# prec_3V_LDO.net
KiCad netlist of a schematic drawn in Altium Designer
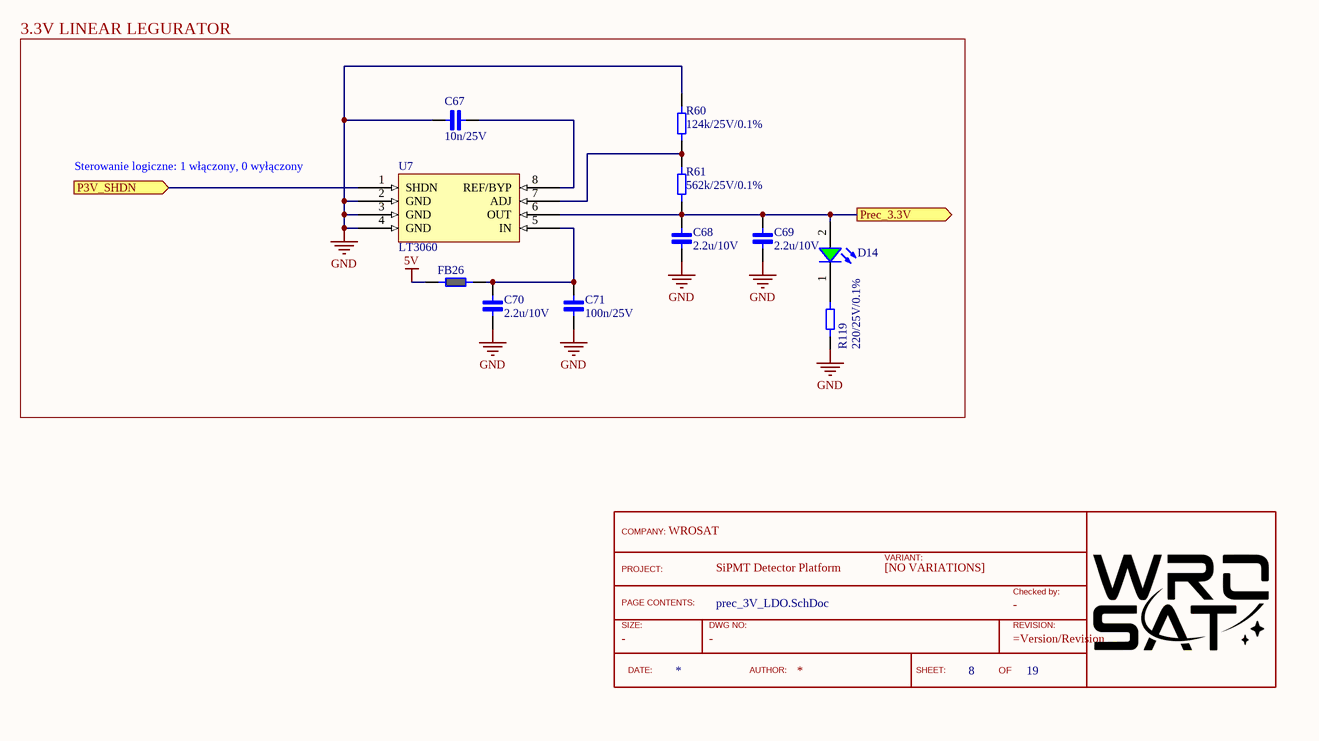
[diagram p0: prec_3V_LDO.SchDoc]

(export (version "E")
  (design (tool "Eeschema 10.0.6"))
  (components
    (comp (ref "C67")
      (value "10n/25V")
      (footprint "Cap_0402")
      (description "Ceramic Capacitor 10n / 0402 / 25V / ±5%, Wurth Elektronik MLCC")
      (libsource (lib "Cubesat_lib") (part "Cap_0402_10n"))
    )
    (comp (ref "C68")
      (value "2.2u/10V")
      (footprint "Cap_0402")
      (description "Ceramic Capacitor 2.2uF / 0402 / 10V / ±5%, Wurth Elektronik MLCC")
      (libsource (lib "Cubesat_lib") (part "Cap_0402_2.2u"))
    )
    (comp (ref "C69")
      (value "2.2u/10V")
      (footprint "Cap_0402")
      (description "Ceramic Capacitor 2.2uF / 0402 / 10V / ±5%, Wurth Elektronik MLCC")
      (libsource (lib "Cubesat_lib") (part "Cap_0402_2.2u"))
    )
    (comp (ref "C70")
      (value "2.2u/10V")
      (footprint "Cap_0402")
      (description "Ceramic Capacitor 2.2uF / 0402 / 10V / ±5%, Wurth Elektronik MLCC")
      (libsource (lib "Cubesat_lib") (part "Cap_0402_2.2u"))
    )
    (comp (ref "C71")
      (value "100n/25V")
      (footprint "Cap_0402")
      (description "Ceramic Capacitor 100n / 0402 / 25V / ±5%, Wurth Elektronik MLCC")
      (libsource (lib "Cubesat_lib") (part "Cap_0402_100n"))
    )
    (comp (ref "D14")
      (value "Green, 3.2V")
      (footprint "WL-SMCW_0603_H=0.7mm")
      (description "WL-SMCW SMT Mono-color Chip LED Waterclear, size 0603, Green, 3.2V, 140deg")
      (fields (field (name "PART NUMBER") "150060GS75000") (field (name "PUBLISHER") "Wurth Elektronik"))
      (libsource (lib "LEDS") (part "150060GS75000"))
    )
    (comp (ref "FB26")
      (value "Ferrite_bead_0402")
      (footprint "FERRITE_0402")
      (description "Ferrite bead, wurth 74269241102")
      (libsource (lib "Cubesat_lib") (part "Ferrite_bead_0402"))
    )
    (comp (ref "R60")
      (value "124k/25V/0.1%")
      (footprint "RES_0402")
      (description "Vishay, thin film resistor 124k/25V/0.1%")
      (libsource (lib "Cubesat_lib") (part "Res_0402_124k"))
    )
    (comp (ref "R61")
      (value "562k/25V/0.1%")
      (footprint "RES_0402")
      (description "Vishay, thin film resistor 562k/25V/0.1%")
      (libsource (lib "Cubesat_lib") (part "Res_0402_562k"))
    )
    (comp (ref "R119")
      (value "220/25V/0.1%")
      (footprint "RES_0402")
      (description "Vishay, thin film resistor 1/25V/0.1%")
      (libsource (lib "Cubesat_lib") (part "Res_0402_1"))
    )
    (comp (ref "U7")
      (value "LT3060")
      (footprint "TS8")
      (description "45V VIN, Micropower,\r\nLow Noise, 100mA Low\r\nDropout, Linear Regulator")
      (libsource (lib "Cubesat_lib") (part "Lt3060"))
    )
  )
  (nets
    (net (code "1") (name "/P3V_SHDN") (class "Default")
      (node (ref "U7") (pin "1") (pinfunction "SHDN_1") (pintype "input"))
    )
    (net (code "2") (name "/Prec_3.3V") (class "Default")
      (node (ref "C68") (pin "2") (pinfunction "2_2") (pintype "passive"))
      (node (ref "C69") (pin "2") (pinfunction "2_2") (pintype "passive"))
      (node (ref "D14") (pin "2") (pinfunction "A_2") (pintype "passive"))
      (node (ref "R61") (pin "1") (pinfunction "1_1") (pintype "passive"))
      (node (ref "U7") (pin "6") (pinfunction "OUT_6") (pintype "input"))
    )
    (net (code "3") (name "5V") (class "Default")
      (node (ref "FB26") (pin "1") (pinfunction "1_1") (pintype "passive"))
    )
    (net (code "4") (name "GND") (class "Default")
      (node (ref "C67") (pin "1") (pinfunction "1_1") (pintype "passive"))
      (node (ref "C68") (pin "1") (pinfunction "1_1") (pintype "passive"))
      (node (ref "C69") (pin "1") (pinfunction "1_1") (pintype "passive"))
      (node (ref "C70") (pin "1") (pinfunction "1_1") (pintype "passive"))
      (node (ref "C71") (pin "1") (pinfunction "1_1") (pintype "passive"))
      (node (ref "R119") (pin "1") (pinfunction "1_1") (pintype "passive"))
      (node (ref "R60") (pin "2") (pinfunction "2_2") (pintype "passive"))
      (node (ref "U7") (pin "2") (pinfunction "GND_2") (pintype "input"))
      (node (ref "U7") (pin "3") (pinfunction "GND_3") (pintype "input"))
      (node (ref "U7") (pin "4") (pinfunction "GND_4") (pintype "input"))
    )
    (net (code "5") (name "Net-(D14-K)") (class "Default")
      (node (ref "D14") (pin "1") (pinfunction "K_1") (pintype "passive"))
      (node (ref "R119") (pin "2") (pinfunction "2_2") (pintype "passive"))
    )
    (net (code "6") (name "Net-(U7-ADJ)") (class "Default")
      (node (ref "R60") (pin "1") (pinfunction "1_1") (pintype "passive"))
      (node (ref "R61") (pin "2") (pinfunction "2_2") (pintype "passive"))
      (node (ref "U7") (pin "7") (pinfunction "ADJ_7") (pintype "input"))
    )
    (net (code "7") (name "Net-(U7-IN)") (class "Default")
      (node (ref "C70") (pin "2") (pinfunction "2_2") (pintype "passive"))
      (node (ref "C71") (pin "2") (pinfunction "2_2") (pintype "passive"))
      (node (ref "FB26") (pin "2") (pinfunction "2_2") (pintype "passive"))
      (node (ref "U7") (pin "5") (pinfunction "IN_5") (pintype "input"))
    )
    (net (code "8") (name "Net-(U7-REF{slash}BYP)") (class "Default")
      (node (ref "C67") (pin "2") (pinfunction "2_2") (pintype "passive"))
      (node (ref "U7") (pin "8") (pinfunction "REF/BYP_8") (pintype "input"))
    )
  )
)
